# Receiver_Design_PCB.net
KiCad netlist of a schematic drawn in Altium Designer
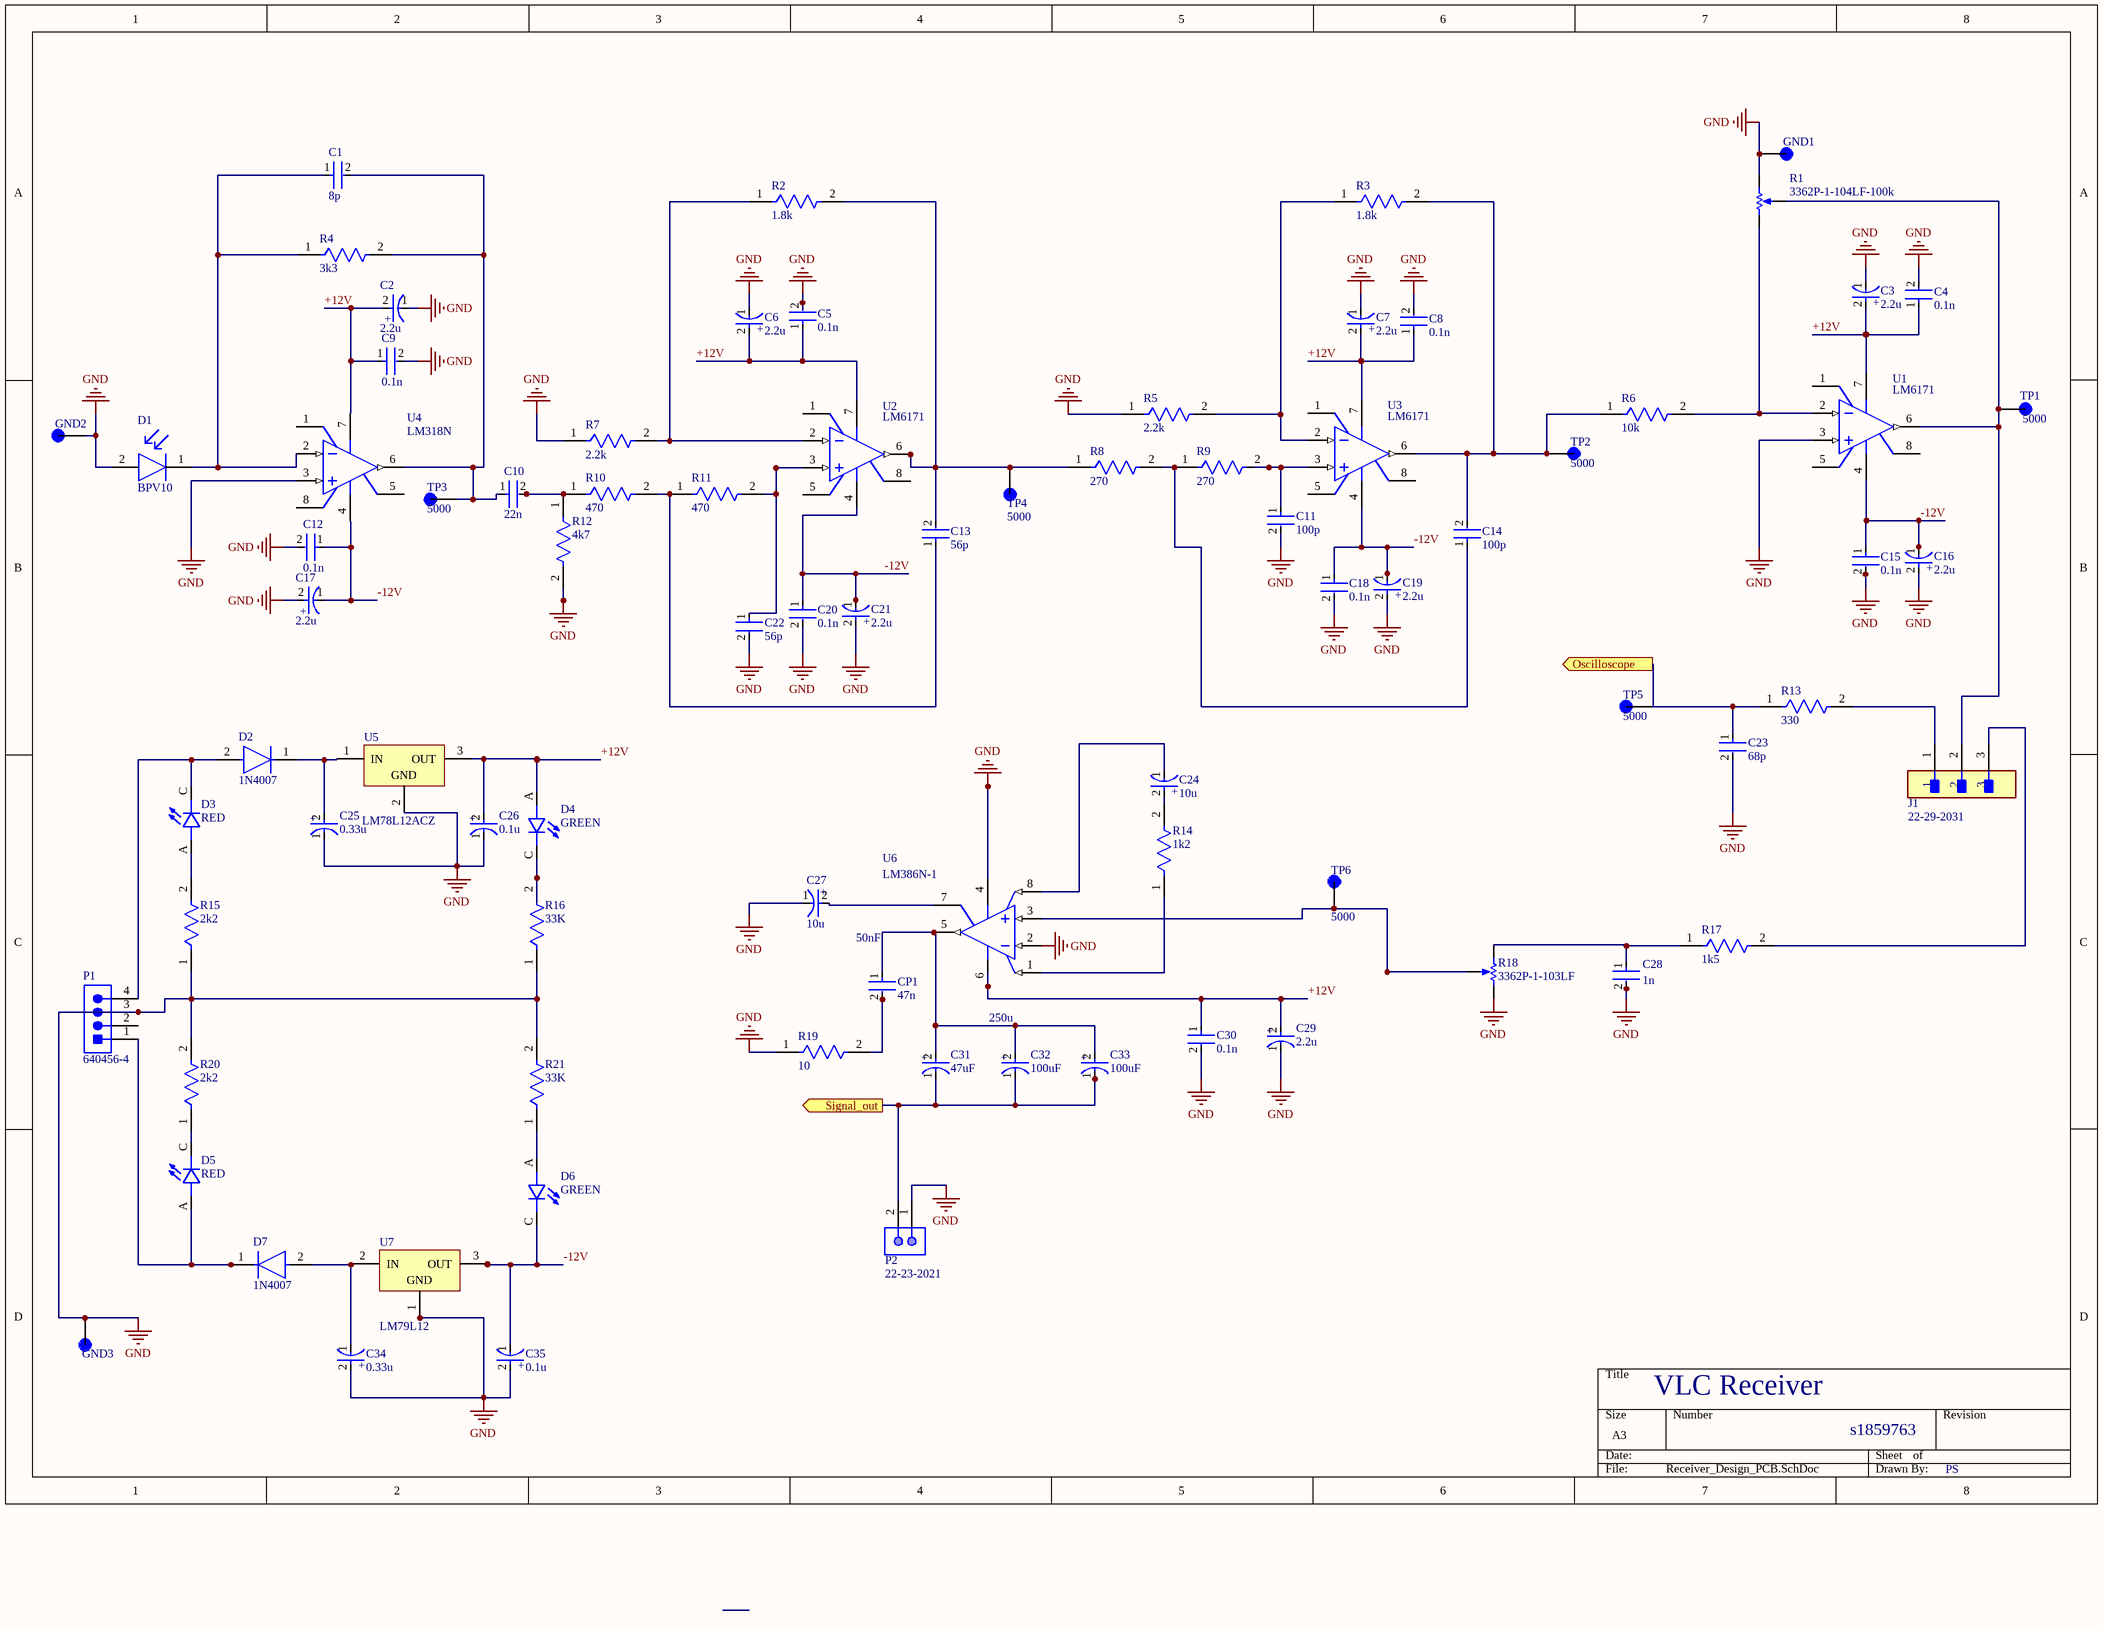
[diagram p0: Receiver_Design_PCB.SchDoc]

(export (version "E")
  (design (tool "Eeschema 10.0.6"))
  (components
    (comp (ref "C1")
      (value "8p")
      (footprint "FP-K15H5-MFG")
      (description "CAP CER 0.1UF 50V X7R RADIAL")
      (fields (field (name "TOLERANCE") "10%") (field (name "VOLTAGE") "50V"))
      (libsource (lib "Altium Content Vault") (part "02cd4be3c70576c341d710602a673aa"))
    )
    (comp (ref "C2")
      (value "2.2u")
      (footprint "FP-TAP106K016SCS-MFG")
      (description "CAP TANT 10UF 10% 16V RADIAL")
      (fields (field (name "TOLERANCE") "10%") (field (name "VOLTAGE") "35V"))
      (libsource (lib "Altium Content Vault") (part "cf48714ba7e38822c1575c7ec0b6d1f"))
    )
    (comp (ref "C3")
      (value "2.2u")
      (footprint "FP-TAP106K016SCS-MFG")
      (description "CAP TANT 10UF 10% 16V RADIAL")
      (fields (field (name "TOLERANCE") "10%") (field (name "VOLTAGE") "35V"))
      (libsource (lib "Altium Content Vault") (part "cf48714ba7e38822c1575c7ec0b6d1f"))
    )
    (comp (ref "C4")
      (value "0.1n")
      (footprint "FP-K15H5-MFG")
      (description "CAP CER 0.1UF 50V X7R RADIAL")
      (fields (field (name "TOLERANCE") "10%") (field (name "VOLTAGE") "50V"))
      (libsource (lib "Altium Content Vault") (part "02cd4be3c70576c341d710602a673aa"))
    )
    (comp (ref "C5")
      (value "0.1n")
      (footprint "FP-K15H5-MFG")
      (description "CAP CER 0.1UF 50V X7R RADIAL")
      (fields (field (name "TOLERANCE") "10%") (field (name "VOLTAGE") "50V"))
      (libsource (lib "Altium Content Vault") (part "02cd4be3c70576c341d710602a673aa"))
    )
    (comp (ref "C6")
      (value "2.2u")
      (footprint "FP-TAP106K016SCS-MFG")
      (description "CAP TANT 10UF 10% 16V RADIAL")
      (fields (field (name "TOLERANCE") "10%") (field (name "VOLTAGE") "35V"))
      (libsource (lib "Altium Content Vault") (part "cf48714ba7e38822c1575c7ec0b6d1f"))
    )
    (comp (ref "C7")
      (value "2.2u")
      (footprint "FP-TAP106K016SCS-MFG")
      (description "CAP TANT 10UF 10% 16V RADIAL")
      (fields (field (name "TOLERANCE") "10%") (field (name "VOLTAGE") "35V"))
      (libsource (lib "Altium Content Vault") (part "cf48714ba7e38822c1575c7ec0b6d1f"))
    )
    (comp (ref "C8")
      (value "0.1n")
      (footprint "FP-K15H5-MFG")
      (description "CAP CER 0.1UF 50V X7R RADIAL")
      (fields (field (name "TOLERANCE") "10%") (field (name "VOLTAGE") "50V"))
      (libsource (lib "Altium Content Vault") (part "02cd4be3c70576c341d710602a673aa"))
    )
    (comp (ref "C9")
      (value "0.1n")
      (footprint "FP-K15H5-MFG")
      (description "CAP CER 0.1UF 50V X7R RADIAL")
      (fields (field (name "TOLERANCE") "10%") (field (name "VOLTAGE") "50V"))
      (libsource (lib "Altium Content Vault") (part "02cd4be3c70576c341d710602a673aa"))
    )
    (comp (ref "C10")
      (value "22n")
      (footprint "FP-K15H5-MFG")
      (description "CAP CER 0.1UF 50V X7R RADIAL")
      (fields (field (name "TOLERANCE") "10%") (field (name "VOLTAGE") "50V"))
      (libsource (lib "Altium Content Vault") (part "02cd4be3c70576c341d710602a673aa"))
    )
    (comp (ref "C11")
      (value "100p")
      (footprint "FP-K15H5-MFG")
      (description "CAP CER 0.1UF 50V X7R RADIAL")
      (fields (field (name "TOLERANCE") "10%") (field (name "VOLTAGE") "50V"))
      (libsource (lib "Altium Content Vault") (part "02cd4be3c70576c341d710602a673aa"))
    )
    (comp (ref "C12")
      (value "0.1n")
      (footprint "FP-K15H5-MFG")
      (description "CAP CER 0.1UF 50V X7R RADIAL")
      (fields (field (name "TOLERANCE") "10%") (field (name "VOLTAGE") "50V"))
      (libsource (lib "Altium Content Vault") (part "02cd4be3c70576c341d710602a673aa"))
    )
    (comp (ref "C13")
      (value "56p")
      (footprint "FP-K15H5-MFG")
      (description "CAP CER 0.1UF 50V X7R RADIAL")
      (fields (field (name "TOLERANCE") "10%") (field (name "VOLTAGE") "50V"))
      (libsource (lib "Altium Content Vault") (part "02cd4be3c70576c341d710602a673aa"))
    )
    (comp (ref "C14")
      (value "100p")
      (footprint "FP-K15H5-MFG")
      (description "CAP CER 0.1UF 50V X7R RADIAL")
      (fields (field (name "TOLERANCE") "10%") (field (name "VOLTAGE") "50V"))
      (libsource (lib "Altium Content Vault") (part "02cd4be3c70576c341d710602a673aa"))
    )
    (comp (ref "C15")
      (value "0.1n")
      (footprint "FP-K15H5-MFG")
      (description "CAP CER 0.1UF 50V X7R RADIAL")
      (fields (field (name "TOLERANCE") "10%") (field (name "VOLTAGE") "50V"))
      (libsource (lib "Altium Content Vault") (part "02cd4be3c70576c341d710602a673aa"))
    )
    (comp (ref "C16")
      (value "2.2u")
      (footprint "FP-TAP106K016SCS-MFG")
      (description "CAP TANT 10UF 10% 16V RADIAL")
      (fields (field (name "TOLERANCE") "10%") (field (name "VOLTAGE") "35V"))
      (libsource (lib "Altium Content Vault") (part "cf48714ba7e38822c1575c7ec0b6d1f"))
    )
    (comp (ref "C17")
      (value "2.2u")
      (footprint "FP-TAP106K016SCS-MFG")
      (description "CAP TANT 10UF 10% 16V RADIAL")
      (fields (field (name "TOLERANCE") "10%") (field (name "VOLTAGE") "35V"))
      (libsource (lib "Altium Content Vault") (part "cf48714ba7e38822c1575c7ec0b6d1f"))
    )
    (comp (ref "C18")
      (value "0.1n")
      (footprint "FP-K15H5-MFG")
      (description "CAP CER 0.1UF 50V X7R RADIAL")
      (fields (field (name "TOLERANCE") "10%") (field (name "VOLTAGE") "50V"))
      (libsource (lib "Altium Content Vault") (part "02cd4be3c70576c341d710602a673aa"))
    )
    (comp (ref "C19")
      (value "2.2u")
      (footprint "FP-TAP106K016SCS-MFG")
      (description "CAP TANT 10UF 10% 16V RADIAL")
      (fields (field (name "TOLERANCE") "10%") (field (name "VOLTAGE") "35V"))
      (libsource (lib "Altium Content Vault") (part "cf48714ba7e38822c1575c7ec0b6d1f"))
    )
    (comp (ref "C20")
      (value "0.1n")
      (footprint "FP-K15H5-MFG")
      (description "CAP CER 0.1UF 50V X7R RADIAL")
      (fields (field (name "TOLERANCE") "10%") (field (name "VOLTAGE") "50V"))
      (libsource (lib "Altium Content Vault") (part "02cd4be3c70576c341d710602a673aa"))
    )
    (comp (ref "C21")
      (value "2.2u")
      (footprint "FP-TAP106K016SCS-MFG")
      (description "CAP TANT 10UF 10% 16V RADIAL")
      (fields (field (name "TOLERANCE") "10%") (field (name "VOLTAGE") "35V"))
      (libsource (lib "Altium Content Vault") (part "cf48714ba7e38822c1575c7ec0b6d1f"))
    )
    (comp (ref "C22")
      (value "56p")
      (footprint "FP-K15H5-MFG")
      (description "CAP CER 0.1UF 50V X7R RADIAL")
      (fields (field (name "TOLERANCE") "10%") (field (name "VOLTAGE") "50V"))
      (libsource (lib "Altium Content Vault") (part "02cd4be3c70576c341d710602a673aa"))
    )
    (comp (ref "C23")
      (value "68p")
      (footprint "FP-K15H5-MFG")
      (description "CAP CER 0.1UF 50V X7R RADIAL")
      (fields (field (name "TOLERANCE") "10%") (field (name "VOLTAGE") "50V"))
      (libsource (lib "Altium Content Vault") (part "02cd4be3c70576c341d710602a673aa"))
    )
    (comp (ref "C24")
      (value "10u")
      (footprint "FP-RAD-TH-D_8_0_5-L_11_5-MFG")
      (description "Aluminum Electrolytic Capacitors (Radial Lead Type) AEC-Q200 Qualified 47uF ±20% 63V")
      (fields (field (name "TOLERANCE") "20%"))
      (libsource (lib "Altium Content Vault") (part "203bc49f2ac43e59fd269a8c329ed05"))
    )
    (comp (ref "C25")
      (value "0.33u")
      (footprint "FP-TAP106K016SCS-MFG")
      (description "CAP TANT 10UF 10% 16V RADIAL")
      (fields (field (name "TOLERANCE") "10%") (field (name "VOLTAGE") "35V"))
      (libsource (lib "Altium Content Vault") (part "cf48714ba7e38822c1575c7ec0b6d1f"))
    )
    (comp (ref "C26")
      (value "0.1u")
      (footprint "FP-TAP106K016SCS-MFG")
      (description "CAP TANT 10UF 10% 16V RADIAL")
      (fields (field (name "TOLERANCE") "10%") (field (name "VOLTAGE") "35V"))
      (libsource (lib "Altium Content Vault") (part "cf48714ba7e38822c1575c7ec0b6d1f"))
    )
    (comp (ref "C27")
      (value "10u")
      (footprint "FP-RAD-TH-D_8_0_5-L_11_5-MFG")
      (description "Aluminum Electrolytic Capacitors (Radial Lead Type) AEC-Q200 Qualified 47uF ±20% 63V")
      (fields (field (name "TOLERANCE") "20%"))
      (libsource (lib "Altium Content Vault") (part "203bc49f2ac43e59fd269a8c329ed05"))
    )
    (comp (ref "C28")
      (value "1n")
      (footprint "FP-K15H5-MFG")
      (description "CAP CER 0.1UF 50V X7R RADIAL")
      (fields (field (name "TOLERANCE") "10%") (field (name "VOLTAGE") "50V"))
      (libsource (lib "Altium Content Vault") (part "02cd4be3c70576c341d710602a673aa"))
    )
    (comp (ref "C29")
      (value "2.2u")
      (footprint "FP-TAP106K016SCS-MFG")
      (description "CAP TANT 10UF 10% 16V RADIAL")
      (fields (field (name "TOLERANCE") "10%") (field (name "VOLTAGE") "35V"))
      (libsource (lib "Altium Content Vault") (part "cf48714ba7e38822c1575c7ec0b6d1f"))
    )
    (comp (ref "C30")
      (value "0.1n")
      (footprint "FP-K15H5-MFG")
      (description "CAP CER 0.1UF 50V X7R RADIAL")
      (fields (field (name "TOLERANCE") "10%") (field (name "VOLTAGE") "50V"))
      (libsource (lib "Altium Content Vault") (part "02cd4be3c70576c341d710602a673aa"))
    )
    (comp (ref "C31")
      (value "47uF")
      (footprint "FP-RAD-TH-D_8_0_5-L_11_5-MFG")
      (description "Aluminum Electrolytic Capacitors (Radial Lead Type) AEC-Q200 Qualified 47uF ±20% 63V")
      (fields (field (name "TOLERANCE") "20%"))
      (libsource (lib "Altium Content Vault") (part "203bc49f2ac43e59fd269a8c329ed05"))
    )
    (comp (ref "C32")
      (value "100uF")
      (footprint "FP-EEU-FR1H101B-MFG")
      (description "CAP ALUM 100UF 20% 50V RADIAL")
      (fields (field (name "TOLERANCE") "20%"))
      (libsource (lib "Altium Content Vault") (part "cf48714ba7e38822c1575c7ec0b6d1f"))
    )
    (comp (ref "C33")
      (value "100uF")
      (footprint "FP-EEU-FR1H101B-MFG")
      (description "CAP ALUM 100UF 20% 50V RADIAL")
      (fields (field (name "TOLERANCE") "20%"))
      (libsource (lib "Altium Content Vault") (part "cf48714ba7e38822c1575c7ec0b6d1f"))
    )
    (comp (ref "C34")
      (value "0.33u")
      (footprint "FP-TAP106K016SCS-MFG")
      (description "CAP TANT 10UF 10% 16V RADIAL")
      (fields (field (name "TOLERANCE") "10%") (field (name "VOLTAGE") "35V"))
      (libsource (lib "Altium Content Vault") (part "cf48714ba7e38822c1575c7ec0b6d1f"))
    )
    (comp (ref "C35")
      (value "0.1u")
      (footprint "FP-TAP106K016SCS-MFG")
      (description "CAP TANT 10UF 10% 16V RADIAL")
      (fields (field (name "TOLERANCE") "10%") (field (name "VOLTAGE") "35V"))
      (libsource (lib "Altium Content Vault") (part "cf48714ba7e38822c1575c7ec0b6d1f"))
    )
    (comp (ref "CP1")
      (value "47n")
      (footprint "FP-R82DC4100DQ60J-MFG")
      (description "CAP FILM 1UF 5% 63VDC RADIAL")
      (fields (field (name "VOLTAGE") "63V") (field (name "TOLERANCE") "5%"))
      (libsource (lib "Altium Content Vault") (part "11868f565c42a9108669ba33697ecf6"))
    )
    (comp (ref "D1")
      (value "BPV10")
      (footprint "FP-6_544-5185_02-4-MFG")
      (description "SENSOR PHOTODIODE 940NM RADIAL")
      (fields
        (field (name "OCTOPART") "https://octopart.com/bpv10-vishay-39728465")
        (field (name "MANUFACTURER") "Vishay")
      )
      (libsource (lib "Altium Content Vault") (part "4feccf841c7a0f3ce322b942935f426"))
    )
    (comp (ref "D2")
      (value "1N4007")
      (footprint "FP-1N4007-MFG")
      (description "Rectifier diode 1000 V 1 A DO-41, ,")
      (fields
        (field (name "MANUFACTURER") "Diotec")
        (field (name "OCTOPART") "https://octopart.com/1n4007-diotec-4040411")
      )
      (libsource (lib "Altium Content Vault") (part "d7152d700b627762746794eb795d46e"))
    )
    (comp (ref "D3")
      (value "RED")
      (footprint "LEDRD254W57D500H1070")
      (fields (field (name "MP") "L08R5000Q1") (field (name "MF") "LED Technology"))
      (libsource (lib "L08R5000Q1") (part "L08R5000Q1"))
    )
    (comp (ref "D4")
      (value "GREEN")
      (footprint "LEDRD254W57D500H1070")
      (fields (field (name "MP") "L08R5000Q1") (field (name "MF") "LED Technology"))
      (libsource (lib "L08R5000Q1") (part "L08R5000Q1"))
    )
    (comp (ref "D5")
      (value "RED")
      (footprint "LEDRD254W57D500H1070")
      (fields (field (name "MP") "L08R5000Q1") (field (name "MF") "LED Technology"))
      (libsource (lib "L08R5000Q1") (part "L08R5000Q1"))
    )
    (comp (ref "D6")
      (value "GREEN")
      (footprint "LEDRD254W57D500H1070")
      (fields (field (name "MP") "L08R5000Q1") (field (name "MF") "LED Technology"))
      (libsource (lib "L08R5000Q1") (part "L08R5000Q1"))
    )
    (comp (ref "D7")
      (value "1N4007")
      (footprint "FP-1N4007-MFG")
      (description "Rectifier diode 1000 V 1 A DO-41, ,")
      (fields
        (field (name "MANUFACTURER") "Diotec")
        (field (name "OCTOPART") "https://octopart.com/1n4007-diotec-4040411")
      )
      (libsource (lib "Altium Content Vault") (part "d7152d700b627762746794eb795d46e"))
    )
    (comp (ref "GND1")
      (value "~")
      (footprint "KEYSTONE_5000")
      (fields (field (name "MF") "Keystone Electronics") (field (name "MP") "5000"))
      (libsource (lib "5000") (part "5000"))
    )
    (comp (ref "GND2")
      (value "~")
      (footprint "KEYSTONE_5000")
      (fields (field (name "MF") "Keystone Electronics") (field (name "MP") "5000"))
      (libsource (lib "5000") (part "5000"))
    )
    (comp (ref "GND3")
      (value "~")
      (footprint "KEYSTONE_5000")
      (fields (field (name "MF") "Keystone Electronics") (field (name "MP") "5000"))
      (libsource (lib "5000") (part "5000"))
    )
    (comp (ref "J1")
      (value "22-29-2031")
      (footprint "FP-22-29-2031-MFG")
      (description "CONN HEADER VERT 3POS 2.54MM")
      (libsource (lib "Altium Content Vault") (part "0d3f023dd272f625e17a2be33dea85f"))
    )
    (comp (ref "P1")
      (value "640456-4")
      (footprint "TECO-640456-4")
      (description "Male Header, Pitch 2.54 mm, 1 x 4 Position, Height 10.03 mm, Tail Length 3.56 mm, RoHS, Bulk")
      (fields (field (name "MANUFACTURER") "TE Connectivity"))
      (libsource (lib "Altium Content Vault") (part "CN-1P-M-R4"))
    )
    (comp (ref "P2")
      (value "22-23-2021")
      (footprint "MOLX-22-23-2021_V")
      (libsource (lib "Altium Content Vault") (part "CN-1P-M-R2"))
    )
    (comp (ref "R1")
      (value "3362P-1-104LF-100k")
      (footprint "BOUR-3362P")
      (description "Square Trimpot(R) Trimming Potentiometer, 10 KOhm, 300 V, -55 to 125 degC, 3-Pin THD, RoHS, Tube")
      (fields (field (name "TOLERANCE") "1%"))
      (libsource (lib "Altium Content Vault") (part "RES-POT-3"))
    )
    (comp (ref "R2")
      (value "1.8k")
      (footprint "FP-MRS25-MFG")
      (description "RES 1K OHM 0.6W 1% AXIAL")
      (fields (field (name "TOLERANCE") "1%"))
      (libsource (lib "Altium Content Vault") (part "1029c3af85768c4190bb7ad29bc67b5"))
    )
    (comp (ref "R3")
      (value "1.8k")
      (footprint "FP-MRS25-MFG")
      (description "RES 1K OHM 0.6W 1% AXIAL")
      (fields (field (name "TOLERANCE") "1%"))
      (libsource (lib "Altium Content Vault") (part "1029c3af85768c4190bb7ad29bc67b5"))
    )
    (comp (ref "R4")
      (value "3k3")
      (footprint "FP-MRS25-MFG")
      (description "RES 1K OHM 0.6W 1% AXIAL")
      (fields (field (name "TOLERANCE") "1%"))
      (libsource (lib "Altium Content Vault") (part "1029c3af85768c4190bb7ad29bc67b5"))
    )
    (comp (ref "R5")
      (value "2.2k")
      (footprint "FP-MRS25-MFG")
      (description "RES 1K OHM 0.6W 1% AXIAL")
      (fields (field (name "TOLERANCE") "1%"))
      (libsource (lib "Altium Content Vault") (part "1029c3af85768c4190bb7ad29bc67b5"))
    )
    (comp (ref "R6")
      (value "10k")
      (footprint "FP-MRS25-MFG")
      (description "RES 1K OHM 0.6W 1% AXIAL")
      (fields (field (name "TOLERANCE") "1%"))
      (libsource (lib "Altium Content Vault") (part "1029c3af85768c4190bb7ad29bc67b5"))
    )
    (comp (ref "R7")
      (value "2.2k")
      (footprint "FP-MRS25-MFG")
      (description "RES 1K OHM 0.6W 1% AXIAL")
      (fields (field (name "TOLERANCE") "1%"))
      (libsource (lib "Altium Content Vault") (part "1029c3af85768c4190bb7ad29bc67b5"))
    )
    (comp (ref "R8")
      (value "270")
      (footprint "FP-MRS25-MFG")
      (description "RES 1K OHM 0.6W 1% AXIAL")
      (fields (field (name "TOLERANCE") "1%"))
      (libsource (lib "Altium Content Vault") (part "1029c3af85768c4190bb7ad29bc67b5"))
    )
    (comp (ref "R9")
      (value "270")
      (footprint "FP-MRS25-MFG")
      (description "RES 1K OHM 0.6W 1% AXIAL")
      (fields (field (name "TOLERANCE") "1%"))
      (libsource (lib "Altium Content Vault") (part "1029c3af85768c4190bb7ad29bc67b5"))
    )
    (comp (ref "R10")
      (value "470")
      (footprint "FP-MRS25-MFG")
      (description "RES 1K OHM 0.6W 1% AXIAL")
      (fields (field (name "TOLERANCE") "1%"))
      (libsource (lib "Altium Content Vault") (part "1029c3af85768c4190bb7ad29bc67b5"))
    )
    (comp (ref "R11")
      (value "470")
      (footprint "FP-MRS25-MFG")
      (description "RES 1K OHM 0.6W 1% AXIAL")
      (fields (field (name "TOLERANCE") "1%"))
      (libsource (lib "Altium Content Vault") (part "1029c3af85768c4190bb7ad29bc67b5"))
    )
    (comp (ref "R12")
      (value "4k7")
      (footprint "FP-MRS25-MFG")
      (description "RES 1K OHM 0.6W 1% AXIAL")
      (fields (field (name "TOLERANCE") "1%"))
      (libsource (lib "Altium Content Vault") (part "1029c3af85768c4190bb7ad29bc67b5"))
    )
    (comp (ref "R13")
      (value "330")
      (footprint "FP-MRS25-MFG")
      (description "RES 1K OHM 0.6W 1% AXIAL")
      (fields (field (name "TOLERANCE") "1%"))
      (libsource (lib "Altium Content Vault") (part "1029c3af85768c4190bb7ad29bc67b5"))
    )
    (comp (ref "R14")
      (value "1k2")
      (footprint "FP-MRS25-MFG")
      (description "RES 1K OHM 0.6W 1% AXIAL")
      (fields (field (name "TOLERANCE") "1%"))
      (libsource (lib "Altium Content Vault") (part "1029c3af85768c4190bb7ad29bc67b5"))
    )
    (comp (ref "R15")
      (value "2k2")
      (footprint "FP-MRS25-MFG")
      (description "RES 1K OHM 0.6W 1% AXIAL")
      (fields (field (name "TOLERANCE") "1%"))
      (libsource (lib "Altium Content Vault") (part "1029c3af85768c4190bb7ad29bc67b5"))
    )
    (comp (ref "R16")
      (value "33K")
      (footprint "FP-MRS25-MFG")
      (description "RES 1K OHM 0.6W 1% AXIAL")
      (fields (field (name "TOLERANCE") "1%"))
      (libsource (lib "Altium Content Vault") (part "1029c3af85768c4190bb7ad29bc67b5"))
    )
    (comp (ref "R17")
      (value "1k5")
      (footprint "FP-MRS25-MFG")
      (description "RES 1K OHM 0.6W 1% AXIAL")
      (fields (field (name "TOLERANCE") "1%"))
      (libsource (lib "Altium Content Vault") (part "1029c3af85768c4190bb7ad29bc67b5"))
    )
    (comp (ref "R18")
      (value "3362P-1-103LF")
      (footprint "BOUR-3362P")
      (description "Square Trimpot(R) Trimming Potentiometer, 10 KOhm, 300 V, -55 to 125 degC, 3-Pin THD, RoHS, Tube")
      (fields (field (name "TOLERANCE") "1%"))
      (libsource (lib "Altium Content Vault") (part "RES-POT-3"))
    )
    (comp (ref "R19")
      (value "10")
      (footprint "FP-MRS25-MFG")
      (description "RES 1K OHM 0.6W 1% AXIAL")
      (fields (field (name "TOLERANCE") "1%"))
      (libsource (lib "Altium Content Vault") (part "1029c3af85768c4190bb7ad29bc67b5"))
    )
    (comp (ref "R20")
      (value "2k2")
      (footprint "FP-MRS25-MFG")
      (description "RES 1K OHM 0.6W 1% AXIAL")
      (fields (field (name "TOLERANCE") "1%"))
      (libsource (lib "Altium Content Vault") (part "1029c3af85768c4190bb7ad29bc67b5"))
    )
    (comp (ref "R21")
      (value "33K")
      (footprint "FP-MRS25-MFG")
      (description "RES 1K OHM 0.6W 1% AXIAL")
      (fields (field (name "TOLERANCE") "1%"))
      (libsource (lib "Altium Content Vault") (part "1029c3af85768c4190bb7ad29bc67b5"))
    )
    (comp (ref "TP1")
      (value "5000")
      (footprint "KEYSTONE_5000")
      (fields (field (name "MF") "Keystone Electronics"))
      (libsource (lib "5000") (part "5000"))
    )
    (comp (ref "TP2")
      (value "5000")
      (footprint "KEYSTONE_5000")
      (fields (field (name "MF") "Keystone Electronics"))
      (libsource (lib "5000") (part "5000"))
    )
    (comp (ref "TP3")
      (value "5000")
      (footprint "KEYSTONE_5000")
      (fields (field (name "MF") "Keystone Electronics"))
      (libsource (lib "5000") (part "5000"))
    )
    (comp (ref "TP4")
      (value "5000")
      (footprint "KEYSTONE_5000")
      (fields (field (name "MF") "Keystone Electronics"))
      (libsource (lib "5000") (part "5000"))
    )
    (comp (ref "TP5")
      (value "5000")
      (footprint "KEYSTONE_5000")
      (fields (field (name "MF") "Keystone Electronics"))
      (libsource (lib "5000") (part "5000"))
    )
    (comp (ref "TP6")
      (value "5000")
      (footprint "KEYSTONE_5000")
      (fields (field (name "MF") "Keystone Electronics"))
      (libsource (lib "5000") (part "5000"))
    )
    (comp (ref "U1")
      (value "LM6171")
      (footprint "P0008A")
      (description "High Speed Low Power Low Distortion Voltage Feedback Amplifier, 8-pin MDIP, Pb-Free")
      (fields (field (name "MANUFACTURER") "Texas Instruments"))
      (libsource (lib "Altium Content Vault") (part "AMP-OPA-LM6171-8"))
    )
    (comp (ref "U2")
      (value "LM6171")
      (footprint "P0008A")
      (description "High Speed Low Power Low Distortion Voltage Feedback Amplifier, 8-pin MDIP, Pb-Free")
      (fields (field (name "MANUFACTURER") "Texas Instruments"))
      (libsource (lib "Altium Content Vault") (part "AMP-OPA-LM6171-8"))
    )
    (comp (ref "U3")
      (value "LM6171")
      (footprint "P0008A")
      (description "High Speed Low Power Low Distortion Voltage Feedback Amplifier, 8-pin MDIP, Pb-Free")
      (fields (field (name "MANUFACTURER") "Texas Instruments"))
      (libsource (lib "Altium Content Vault") (part "AMP-OPA-LM6171-8"))
    )
    (comp (ref "U4")
      (value "LM318N")
      (footprint "P0008A")
      (description "Operational Amplifier, 8-pin MDIP")
      (fields (field (name "MANUFACTURER") "Texas Instruments"))
      (libsource (lib "Altium Content Vault") (part "AMP-OPA-LM118-8"))
    )
    (comp (ref "U5")
      (value "LM78L12ACZ")
      (footprint "TO220")
      (description "Positive Voltage Regulator, 5V, 3-Pin TO-220")
      (libsource (lib "Altium Content Vault") (part "PM-REG-L4940-SIL3"))
    )
    (comp (ref "U6")
      (value "LM386N-1")
      (footprint "TI-P8")
      (description "Low Voltage Audio Power Amplifier, 0 to 70 degC, 8-pin DIP (P8)")
      (fields (field (name "MANUFACTURER") "Texas Instruments"))
      (libsource (lib "Altium Content Vault") (part "TI-LM386undefined"))
    )
    (comp (ref "U7")
      (value "LM79L12")
      (footprint "NDE0003A")
      (description "3-Terminal Negative Regulator, 3-pin TO-220, Pb-Free")
      (fields (field (name "MANUFACTURER") "Texas Instruments"))
      (libsource (lib "Altium Content Vault") (part "PM-REG-LM7905-SIL3"))
    )
  )
  (nets
    (net (code "1") (name "/+12V") (class "Default")
      (node (ref "C2") (pin "2") (pinfunction "A_2") (pintype "passive"))
      (node (ref "C26") (pin "2") (pinfunction "A_2") (pintype "passive"))
      (node (ref "C29") (pin "2") (pinfunction "A_2") (pintype "passive"))
      (node (ref "C3") (pin "2") (pinfunction "A_2") (pintype "passive"))
      (node (ref "C30") (pin "1") (pinfunction "1_1") (pintype "passive"))
      (node (ref "C4") (pin "1") (pinfunction "1_1") (pintype "passive"))
      (node (ref "C5") (pin "1") (pinfunction "1_1") (pintype "passive"))
      (node (ref "C6") (pin "2") (pinfunction "A_2") (pintype "passive"))
      (node (ref "C7") (pin "2") (pinfunction "A_2") (pintype "passive"))
      (node (ref "C8") (pin "1") (pinfunction "1_1") (pintype "passive"))
      (node (ref "C9") (pin "1") (pinfunction "1_1") (pintype "passive"))
      (node (ref "D4") (pin "A") (pinfunction "A_A") (pintype "passive"))
      (node (ref "U1") (pin "7") (pinfunction "V+_7") (pintype "power_in"))
      (node (ref "U2") (pin "7") (pinfunction "V+_7") (pintype "power_in"))
      (node (ref "U3") (pin "7") (pinfunction "V+_7") (pintype "power_in"))
      (node (ref "U4") (pin "7") (pinfunction "V+_7") (pintype "power_in"))
      (node (ref "U5") (pin "3") (pinfunction "OUT_3") (pintype "power_in"))
      (node (ref "U6") (pin "6") (pinfunction "VS_6") (pintype "power_in"))
    )
    (net (code "2") (name "/-12V") (class "Default")
      (node (ref "C12") (pin "1") (pinfunction "1_1") (pintype "passive"))
      (node (ref "C15") (pin "1") (pinfunction "1_1") (pintype "passive"))
      (node (ref "C16") (pin "1") (pinfunction "C_1") (pintype "passive"))
      (node (ref "C17") (pin "1") (pinfunction "C_1") (pintype "passive"))
      (node (ref "C18") (pin "1") (pinfunction "1_1") (pintype "passive"))
      (node (ref "C19") (pin "1") (pinfunction "C_1") (pintype "passive"))
      (node (ref "C20") (pin "1") (pinfunction "1_1") (pintype "passive"))
      (node (ref "C21") (pin "1") (pinfunction "C_1") (pintype "passive"))
      (node (ref "C35") (pin "1") (pinfunction "C_1") (pintype "passive"))
      (node (ref "D6") (pin "C") (pinfunction "C_C") (pintype "passive"))
      (node (ref "U1") (pin "4") (pinfunction "V-_4") (pintype "power_in"))
      (node (ref "U2") (pin "4") (pinfunction "V-_4") (pintype "power_in"))
      (node (ref "U3") (pin "4") (pinfunction "V-_4") (pintype "power_in"))
      (node (ref "U4") (pin "4") (pinfunction "V-_4") (pintype "power_in"))
      (node (ref "U7") (pin "3") (pinfunction "OUT_3") (pintype "power_in"))
    )
    (net (code "3") (name "/Oscilloscope") (class "Default")
      (node (ref "C23") (pin "1") (pinfunction "1_1") (pintype "passive"))
      (node (ref "R13") (pin "1") (pinfunction "1_1") (pintype "passive"))
      (node (ref "TP5") (pin "TP") (pinfunction "TP_TP") (pintype "passive"))
    )
    (net (code "4") (name "/Signal_out") (class "Default")
      (node (ref "C31") (pin "1") (pinfunction "C_1") (pintype "passive"))
      (node (ref "C32") (pin "1") (pinfunction "C_1") (pintype "passive"))
      (node (ref "C33") (pin "1") (pinfunction "C_1") (pintype "passive"))
      (node (ref "P2") (pin "2") (pinfunction "2_2") (pintype "passive"))
    )
    (net (code "5") (name "GND") (class "Default")
      (node (ref "C11") (pin "2") (pinfunction "2_2") (pintype "passive"))
      (node (ref "C12") (pin "2") (pinfunction "2_2") (pintype "passive"))
      (node (ref "C15") (pin "2") (pinfunction "2_2") (pintype "passive"))
      (node (ref "C16") (pin "2") (pinfunction "A_2") (pintype "passive"))
      (node (ref "C17") (pin "2") (pinfunction "A_2") (pintype "passive"))
      (node (ref "C18") (pin "2") (pinfunction "2_2") (pintype "passive"))
      (node (ref "C19") (pin "2") (pinfunction "A_2") (pintype "passive"))
      (node (ref "C2") (pin "1") (pinfunction "C_1") (pintype "passive"))
      (node (ref "C20") (pin "2") (pinfunction "2_2") (pintype "passive"))
      (node (ref "C21") (pin "2") (pinfunction "A_2") (pintype "passive"))
      (node (ref "C22") (pin "2") (pinfunction "2_2") (pintype "passive"))
      (node (ref "C23") (pin "2") (pinfunction "2_2") (pintype "passive"))
      (node (ref "C25") (pin "1") (pinfunction "C_1") (pintype "passive"))
      (node (ref "C26") (pin "1") (pinfunction "C_1") (pintype "passive"))
      (node (ref "C27") (pin "1") (pinfunction "C_1") (pintype "passive"))
      (node (ref "C28") (pin "2") (pinfunction "2_2") (pintype "passive"))
      (node (ref "C29") (pin "1") (pinfunction "C_1") (pintype "passive"))
      (node (ref "C3") (pin "1") (pinfunction "C_1") (pintype "passive"))
      (node (ref "C30") (pin "2") (pinfunction "2_2") (pintype "passive"))
      (node (ref "C34") (pin "2") (pinfunction "A_2") (pintype "passive"))
      (node (ref "C35") (pin "2") (pinfunction "A_2") (pintype "passive"))
      (node (ref "C4") (pin "2") (pinfunction "2_2") (pintype "passive"))
      (node (ref "C5") (pin "2") (pinfunction "2_2") (pintype "passive"))
      (node (ref "C6") (pin "1") (pinfunction "C_1") (pintype "passive"))
      (node (ref "C7") (pin "1") (pinfunction "C_1") (pintype "passive"))
      (node (ref "C8") (pin "2") (pinfunction "2_2") (pintype "passive"))
      (node (ref "C9") (pin "2") (pinfunction "2_2") (pintype "passive"))
      (node (ref "D1") (pin "2") (pinfunction "A_2") (pintype "passive"))
      (node (ref "GND1") (pin "TP") (pinfunction "TP_TP") (pintype "passive"))
      (node (ref "GND2") (pin "TP") (pinfunction "TP_TP") (pintype "passive"))
      (node (ref "GND3") (pin "TP") (pinfunction "TP_TP") (pintype "passive"))
      (node (ref "P1") (pin "3") (pinfunction "3_3") (pintype "passive"))
      (node (ref "P2") (pin "1") (pinfunction "1_1") (pintype "passive"))
      (node (ref "R1") (pin "3") (pinfunction "CW_3") (pintype "passive"))
      (node (ref "R12") (pin "2") (pinfunction "2_2") (pintype "passive"))
      (node (ref "R15") (pin "1") (pinfunction "1_1") (pintype "passive"))
      (node (ref "R16") (pin "1") (pinfunction "1_1") (pintype "passive"))
      (node (ref "R18") (pin "3") (pinfunction "CW_3") (pintype "passive"))
      (node (ref "R19") (pin "1") (pinfunction "1_1") (pintype "passive"))
      (node (ref "R20") (pin "2") (pinfunction "2_2") (pintype "passive"))
      (node (ref "R21") (pin "2") (pinfunction "2_2") (pintype "passive"))
      (node (ref "R5") (pin "1") (pinfunction "1_1") (pintype "passive"))
      (node (ref "R7") (pin "1") (pinfunction "1_1") (pintype "passive"))
      (node (ref "U1") (pin "3") (pinfunction "IN+_3") (pintype "input"))
      (node (ref "U4") (pin "3") (pinfunction "IN+_3") (pintype "input"))
      (node (ref "U5") (pin "2") (pinfunction "GND_2") (pintype "power_in"))
      (node (ref "U6") (pin "2") (pinfunction "IN-_2") (pintype "input"))
      (node (ref "U6") (pin "4") (pinfunction "GND_4") (pintype "power_in"))
      (node (ref "U7") (pin "1") (pinfunction "GND_1") (pintype "power_in"))
    )
    (net (code "6") (name "Net-(C10-Pad2)") (class "Default")
      (node (ref "C10") (pin "2") (pinfunction "2_2") (pintype "passive"))
      (node (ref "R10") (pin "1") (pinfunction "1_1") (pintype "passive"))
      (node (ref "R12") (pin "1") (pinfunction "1_1") (pintype "passive"))
    )
    (net (code "7") (name "Net-(C13-Pad1)") (class "Default")
      (node (ref "C13") (pin "1") (pinfunction "1_1") (pintype "passive"))
      (node (ref "R10") (pin "2") (pinfunction "2_2") (pintype "passive"))
      (node (ref "R11") (pin "1") (pinfunction "1_1") (pintype "passive"))
    )
    (net (code "8") (name "Net-(C14-Pad1)") (class "Default")
      (node (ref "C14") (pin "1") (pinfunction "1_1") (pintype "passive"))
      (node (ref "R8") (pin "2") (pinfunction "2_2") (pintype "passive"))
      (node (ref "R9") (pin "1") (pinfunction "1_1") (pintype "passive"))
    )
    (net (code "9") (name "Net-(C24-A)") (class "Default")
      (node (ref "C24") (pin "2") (pinfunction "A_2") (pintype "passive"))
      (node (ref "R14") (pin "2") (pinfunction "2_2") (pintype "passive"))
    )
    (net (code "10") (name "Net-(C24-C)") (class "Default")
      (node (ref "C24") (pin "1") (pinfunction "C_1") (pintype "passive"))
      (node (ref "U6") (pin "8") (pinfunction "GAIN_8") (pintype "input"))
    )
    (net (code "11") (name "Net-(C25-A)") (class "Default")
      (node (ref "C25") (pin "2") (pinfunction "A_2") (pintype "passive"))
      (node (ref "D2") (pin "1") (pinfunction "C_1") (pintype "passive"))
      (node (ref "U5") (pin "1") (pinfunction "IN_1") (pintype "power_in"))
    )
    (net (code "12") (name "Net-(C27-A)") (class "Default")
      (node (ref "C27") (pin "2") (pinfunction "A_2") (pintype "passive"))
      (node (ref "U6") (pin "7") (pinfunction "BYPASS_7") (pintype "passive"))
    )
    (net (code "13") (name "Net-(C31-A)") (class "Default")
      (node (ref "C31") (pin "2") (pinfunction "A_2") (pintype "passive"))
      (node (ref "C32") (pin "2") (pinfunction "A_2") (pintype "passive"))
      (node (ref "C33") (pin "2") (pinfunction "A_2") (pintype "passive"))
      (node (ref "CP1") (pin "1") (pinfunction "1_1") (pintype "passive"))
      (node (ref "U6") (pin "5") (pinfunction "VOUT_5") (pintype "output"))
    )
    (net (code "14") (name "Net-(C34-C)") (class "Default")
      (node (ref "C34") (pin "1") (pinfunction "C_1") (pintype "passive"))
      (node (ref "D7") (pin "2") (pinfunction "A_2") (pintype "passive"))
      (node (ref "U7") (pin "2") (pinfunction "IN_2") (pintype "power_in"))
    )
    (net (code "15") (name "Net-(CP1-Pad2)") (class "Default")
      (node (ref "CP1") (pin "2") (pinfunction "2_2") (pintype "passive"))
      (node (ref "R19") (pin "2") (pinfunction "2_2") (pintype "passive"))
    )
    (net (code "16") (name "Net-(D1-C)") (class "Default")
      (node (ref "C1") (pin "1") (pinfunction "1_1") (pintype "passive"))
      (node (ref "D1") (pin "1") (pinfunction "C_1") (pintype "passive"))
      (node (ref "R4") (pin "1") (pinfunction "1_1") (pintype "passive"))
      (node (ref "U4") (pin "2") (pinfunction "IN-_2") (pintype "input"))
    )
    (net (code "17") (name "Net-(D2-A)") (class "Default")
      (node (ref "D2") (pin "2") (pinfunction "A_2") (pintype "passive"))
      (node (ref "D3") (pin "C") (pinfunction "C_C") (pintype "passive"))
      (node (ref "P1") (pin "4") (pinfunction "4_4") (pintype "passive"))
    )
    (net (code "18") (name "Net-(D3-PadA)") (class "Default")
      (node (ref "D3") (pin "A") (pinfunction "A_A") (pintype "passive"))
      (node (ref "R15") (pin "2") (pinfunction "2_2") (pintype "passive"))
    )
    (net (code "19") (name "Net-(D4-PadC)") (class "Default")
      (node (ref "D4") (pin "C") (pinfunction "C_C") (pintype "passive"))
      (node (ref "R16") (pin "2") (pinfunction "2_2") (pintype "passive"))
    )
    (net (code "20") (name "Net-(D5-PadC)") (class "Default")
      (node (ref "D5") (pin "C") (pinfunction "C_C") (pintype "passive"))
      (node (ref "R20") (pin "1") (pinfunction "1_1") (pintype "passive"))
    )
    (net (code "21") (name "Net-(D6-PadA)") (class "Default")
      (node (ref "D6") (pin "A") (pinfunction "A_A") (pintype "passive"))
      (node (ref "R21") (pin "1") (pinfunction "1_1") (pintype "passive"))
    )
    (net (code "22") (name "Net-(D7-C)") (class "Default")
      (node (ref "D5") (pin "A") (pinfunction "A_A") (pintype "passive"))
      (node (ref "D7") (pin "1") (pinfunction "C_1") (pintype "passive"))
      (node (ref "P1") (pin "1") (pinfunction "1_1") (pintype "passive"))
    )
    (net (code "23") (name "Net-(J1-Pad1)") (class "Default")
      (node (ref "J1") (pin "1") (pinfunction "1_1") (pintype "passive"))
      (node (ref "R13") (pin "2") (pinfunction "2_2") (pintype "passive"))
    )
    (net (code "24") (name "Net-(J1-Pad3)") (class "Default")
      (node (ref "J1") (pin "3") (pinfunction "3_3") (pintype "passive"))
      (node (ref "R17") (pin "2") (pinfunction "2_2") (pintype "passive"))
    )
    (net (code "25") (name "Net-(R1-CCW)") (class "Default")
      (node (ref "R1") (pin "1") (pinfunction "CCW_1") (pintype "passive"))
      (node (ref "R6") (pin "2") (pinfunction "2_2") (pintype "passive"))
      (node (ref "U1") (pin "2") (pinfunction "IN-_2") (pintype "input"))
    )
    (net (code "26") (name "Net-(R1-S)") (class "Default")
      (node (ref "J1") (pin "2") (pinfunction "2_2") (pintype "passive"))
      (node (ref "R1") (pin "2") (pinfunction "S_2") (pintype "passive"))
      (node (ref "TP1") (pin "TP") (pinfunction "TP_TP") (pintype "passive"))
      (node (ref "U1") (pin "6") (pinfunction "OUT_6") (pintype "output"))
    )
    (net (code "27") (name "Net-(R14-Pad1)") (class "Default")
      (node (ref "R14") (pin "1") (pinfunction "1_1") (pintype "passive"))
      (node (ref "U6") (pin "1") (pinfunction "GAIN_1") (pintype "input"))
    )
    (net (code "28") (name "Net-(R18-CCW)") (class "Default")
      (node (ref "C28") (pin "1") (pinfunction "1_1") (pintype "passive"))
      (node (ref "R17") (pin "1") (pinfunction "1_1") (pintype "passive"))
      (node (ref "R18") (pin "1") (pinfunction "CCW_1") (pintype "passive"))
    )
    (net (code "29") (name "Net-(R18-S)") (class "Default")
      (node (ref "R18") (pin "2") (pinfunction "S_2") (pintype "passive"))
      (node (ref "TP6") (pin "TP") (pinfunction "TP_TP") (pintype "passive"))
      (node (ref "U6") (pin "3") (pinfunction "IN+_3") (pintype "input"))
    )
    (net (code "30") (name "Net-(U2-IN+)") (class "Default")
      (node (ref "C22") (pin "1") (pinfunction "1_1") (pintype "passive"))
      (node (ref "R11") (pin "2") (pinfunction "2_2") (pintype "passive"))
      (node (ref "U2") (pin "3") (pinfunction "IN+_3") (pintype "input"))
    )
    (net (code "31") (name "Net-(U2-IN-)") (class "Default")
      (node (ref "R2") (pin "1") (pinfunction "1_1") (pintype "passive"))
      (node (ref "R7") (pin "2") (pinfunction "2_2") (pintype "passive"))
      (node (ref "U2") (pin "2") (pinfunction "IN-_2") (pintype "input"))
    )
    (net (code "32") (name "Net-(U2-OUT)") (class "Default")
      (node (ref "C13") (pin "2") (pinfunction "2_2") (pintype "passive"))
      (node (ref "R2") (pin "2") (pinfunction "2_2") (pintype "passive"))
      (node (ref "R8") (pin "1") (pinfunction "1_1") (pintype "passive"))
      (node (ref "TP4") (pin "TP") (pinfunction "TP_TP") (pintype "passive"))
      (node (ref "U2") (pin "6") (pinfunction "OUT_6") (pintype "output"))
    )
    (net (code "33") (name "Net-(U3-IN+)") (class "Default")
      (node (ref "C11") (pin "1") (pinfunction "1_1") (pintype "passive"))
      (node (ref "R9") (pin "2") (pinfunction "2_2") (pintype "passive"))
      (node (ref "U3") (pin "3") (pinfunction "IN+_3") (pintype "input"))
    )
    (net (code "34") (name "Net-(U3-IN-)") (class "Default")
      (node (ref "R3") (pin "1") (pinfunction "1_1") (pintype "passive"))
      (node (ref "R5") (pin "2") (pinfunction "2_2") (pintype "passive"))
      (node (ref "U3") (pin "2") (pinfunction "IN-_2") (pintype "input"))
    )
    (net (code "35") (name "Net-(U3-OUT)") (class "Default")
      (node (ref "C14") (pin "2") (pinfunction "2_2") (pintype "passive"))
      (node (ref "R3") (pin "2") (pinfunction "2_2") (pintype "passive"))
      (node (ref "R6") (pin "1") (pinfunction "1_1") (pintype "passive"))
      (node (ref "TP2") (pin "TP") (pinfunction "TP_TP") (pintype "passive"))
      (node (ref "U3") (pin "6") (pinfunction "OUT_6") (pintype "output"))
    )
    (net (code "36") (name "Net-(U4-OUT)") (class "Default")
      (node (ref "C1") (pin "2") (pinfunction "2_2") (pintype "passive"))
      (node (ref "C10") (pin "1") (pinfunction "1_1") (pintype "passive"))
      (node (ref "R4") (pin "2") (pinfunction "2_2") (pintype "passive"))
      (node (ref "TP3") (pin "TP") (pinfunction "TP_TP") (pintype "passive"))
      (node (ref "U4") (pin "6") (pinfunction "OUT_6") (pintype "output"))
    )
    (net (code "37") (name "unconnected-(P1-Pad2)") (class "Default")
      (node (ref "P1") (pin "2") (pinfunction "2_2") (pintype "passive"))
    )
    (net (code "38") (name "unconnected-(U1-NC-Pad1)") (class "Default")
      (node (ref "U1") (pin "1") (pinfunction "NC_1") (pintype "passive"))
    )
    (net (code "39") (name "unconnected-(U1-NC-Pad5)") (class "Default")
      (node (ref "U1") (pin "5") (pinfunction "NC_5") (pintype "passive"))
    )
    (net (code "40") (name "unconnected-(U1-NC-Pad8)") (class "Default")
      (node (ref "U1") (pin "8") (pinfunction "NC_8") (pintype "passive"))
    )
    (net (code "41") (name "unconnected-(U2-NC-Pad1)") (class "Default")
      (node (ref "U2") (pin "1") (pinfunction "NC_1") (pintype "passive"))
    )
    (net (code "42") (name "unconnected-(U2-NC-Pad5)") (class "Default")
      (node (ref "U2") (pin "5") (pinfunction "NC_5") (pintype "passive"))
    )
    (net (code "43") (name "unconnected-(U2-NC-Pad8)") (class "Default")
      (node (ref "U2") (pin "8") (pinfunction "NC_8") (pintype "passive"))
    )
    (net (code "44") (name "unconnected-(U3-NC-Pad1)") (class "Default")
      (node (ref "U3") (pin "1") (pinfunction "NC_1") (pintype "passive"))
    )
    (net (code "45") (name "unconnected-(U3-NC-Pad5)") (class "Default")
      (node (ref "U3") (pin "5") (pinfunction "NC_5") (pintype "passive"))
    )
    (net (code "46") (name "unconnected-(U3-NC-Pad8)") (class "Default")
      (node (ref "U3") (pin "8") (pinfunction "NC_8") (pintype "passive"))
    )
    (net (code "47") (name "unconnected-(U4-BAL{slash}COMP1-Pad1)") (class "Default")
      (node (ref "U4") (pin "1") (pinfunction "BAL/COMP1_1") (pintype "passive"))
    )
    (net (code "48") (name "unconnected-(U4-BAL{slash}COMP3-Pad5)") (class "Default")
      (node (ref "U4") (pin "5") (pinfunction "BAL/COMP3_5") (pintype "passive"))
    )
    (net (code "49") (name "unconnected-(U4-COMP2-Pad8)") (class "Default")
      (node (ref "U4") (pin "8") (pinfunction "COMP2_8") (pintype "passive"))
    )
  )
)
